# tdlf_03_05_2021_server.net
KiCad netlist of a schematic drawn in EAGLE
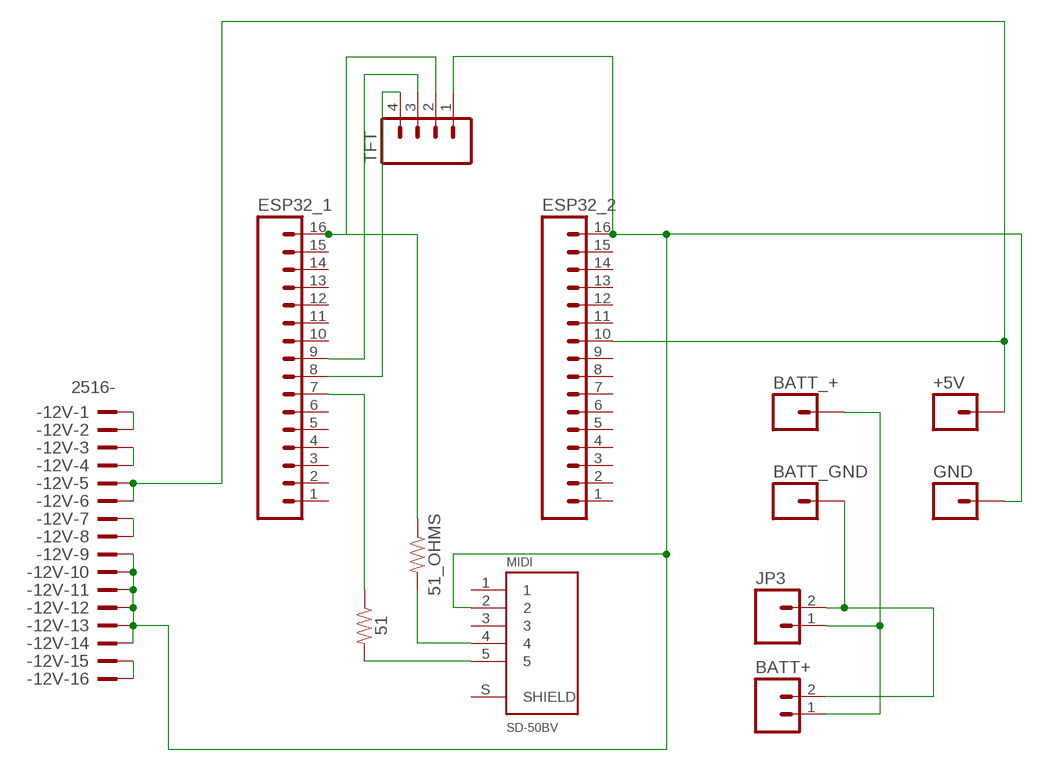
[diagram p0: schematic, sheet 1]

(export (version "E")
  (design (tool "Eeschema 10.0.6"))
  (components
    (comp (ref "+5V")
      (value "M01PTH")
      (footprint "eagle-import:1X01")
      (libsource (lib "eagle-import") (part "M01PTH"))
    )
    (comp (ref "-12V")
      (value "2516-")
      (footprint "eagle-import:PAK100_2500-16")
      (libsource (lib "eagle-import") (part "2516-"))
    )
    (comp (ref "51")
      (value "RESISTOR1206")
      (footprint "eagle-import:1206")
      (libsource (lib "eagle-import") (part "RESISTOR1206"))
    )
    (comp (ref "51_OHMS")
      (value "RESISTOR1206")
      (footprint "eagle-import:1206")
      (libsource (lib "eagle-import") (part "RESISTOR1206"))
    )
    (comp (ref "BATT+")
      (value "M02PTH")
      (footprint "eagle-import:1X02")
      (libsource (lib "eagle-import") (part "M02PTH"))
    )
    (comp (ref "BATT_+")
      (value "M01PTH")
      (footprint "eagle-import:1X01")
      (libsource (lib "eagle-import") (part "M01PTH"))
    )
    (comp (ref "BATT_GND")
      (value "M01PTH")
      (footprint "eagle-import:1X01")
      (libsource (lib "eagle-import") (part "M01PTH"))
    )
    (comp (ref "ESP32_1")
      (value "M16PTH")
      (footprint "eagle-import:1X16")
      (libsource (lib "eagle-import") (part "M16PTH"))
    )
    (comp (ref "ESP32_2")
      (value "M16PTH")
      (footprint "eagle-import:1X16")
      (libsource (lib "eagle-import") (part "M16PTH"))
    )
    (comp (ref "GND")
      (value "M01PTH")
      (footprint "eagle-import:1X01")
      (libsource (lib "eagle-import") (part "M01PTH"))
    )
    (comp (ref "JP3")
      (value "M02PTH")
      (footprint "eagle-import:1X02")
      (libsource (lib "eagle-import") (part "M02PTH"))
    )
    (comp (ref "MIDI")
      (value "SD-50BV")
      (footprint "eagle-import:CUI_SD-50BV")
      (fields (field (name "MF") "CUI Inc"))
      (libsource (lib "eagle-import") (part "SD-50BV"))
    )
    (comp (ref "TFT")
      (value "M04PTH")
      (footprint "eagle-import:1X04")
      (libsource (lib "eagle-import") (part "M04PTH"))
    )
  )
  (nets
    (net (code "1") (name "Net-(-12VA-KL)") (class "Default")
      (node (ref "-12V") (pin "1") (pinfunction "KL_1") (pintype "passive"))
      (node (ref "-12V") (pin "2") (pinfunction "KL_2") (pintype "passive"))
    )
    (net (code "2") (name "Net-(-12VB-KL)") (class "Default")
      (node (ref "-12V") (pin "10") (pinfunction "KL_10") (pintype "passive"))
      (node (ref "-12V") (pin "11") (pinfunction "KL_11") (pintype "passive"))
      (node (ref "-12V") (pin "12") (pinfunction "KL_12") (pintype "passive"))
      (node (ref "-12V") (pin "13") (pinfunction "KL_13") (pintype "passive"))
      (node (ref "-12V") (pin "14") (pinfunction "KL_14") (pintype "passive"))
      (node (ref "-12V") (pin "9") (pinfunction "KL_9") (pintype "passive"))
      (node (ref "ESP32_2") (pin "16") (pinfunction "16_16") (pintype "passive"))
      (node (ref "GND") (pin "1") (pinfunction "1_1") (pintype "passive"))
      (node (ref "MIDI") (pin "2") (pinfunction "2_2") (pintype "passive"))
      (node (ref "TFT") (pin "1") (pinfunction "1_1") (pintype "passive"))
    )
    (net (code "3") (name "Net-(-12VG-KL)") (class "Default")
      (node (ref "-12V") (pin "15") (pinfunction "KL_15") (pintype "passive"))
      (node (ref "-12V") (pin "16") (pinfunction "KL_16") (pintype "passive"))
    )
    (net (code "4") (name "Net-(-12VJ-KL)") (class "Default")
      (node (ref "-12V") (pin "3") (pinfunction "KL_3") (pintype "passive"))
      (node (ref "-12V") (pin "4") (pinfunction "KL_4") (pintype "passive"))
    )
    (net (code "5") (name "Net-(-12VL-KL)") (class "Default")
      (node (ref "+5V") (pin "1") (pinfunction "1_1") (pintype "passive"))
      (node (ref "-12V") (pin "5") (pinfunction "KL_5") (pintype "passive"))
      (node (ref "-12V") (pin "6") (pinfunction "KL_6") (pintype "passive"))
      (node (ref "ESP32_2") (pin "10") (pinfunction "10_10") (pintype "passive"))
    )
    (net (code "6") (name "Net-(-12VN-KL)") (class "Default")
      (node (ref "-12V") (pin "7") (pinfunction "KL_7") (pintype "passive"))
      (node (ref "-12V") (pin "8") (pinfunction "KL_8") (pintype "passive"))
    )
    (net (code "7") (name "Net-(51-Pad1)") (class "Default")
      (node (ref "51") (pin "1") (pinfunction "1_1") (pintype "passive"))
      (node (ref "ESP32_1") (pin "7") (pinfunction "7_7") (pintype "passive"))
    )
    (net (code "8") (name "Net-(51-Pad2)") (class "Default")
      (node (ref "51") (pin "2") (pinfunction "2_2") (pintype "passive"))
      (node (ref "MIDI") (pin "5") (pinfunction "5_5") (pintype "passive"))
    )
    (net (code "9") (name "Net-(51_OHMS-Pad1)") (class "Default")
      (node (ref "51_OHMS") (pin "1") (pinfunction "1_1") (pintype "passive"))
      (node (ref "ESP32_1") (pin "16") (pinfunction "16_16") (pintype "passive"))
      (node (ref "TFT") (pin "2") (pinfunction "2_2") (pintype "passive"))
    )
    (net (code "10") (name "Net-(51_OHMS-Pad2)") (class "Default")
      (node (ref "51_OHMS") (pin "2") (pinfunction "2_2") (pintype "passive"))
      (node (ref "MIDI") (pin "4") (pinfunction "4_4") (pintype "passive"))
    )
    (net (code "11") (name "Net-(BATT+-Pad1)") (class "Default")
      (node (ref "BATT+") (pin "1") (pinfunction "1_1") (pintype "passive"))
      (node (ref "BATT_+") (pin "1") (pinfunction "1_1") (pintype "passive"))
      (node (ref "JP3") (pin "1") (pinfunction "1_1") (pintype "passive"))
    )
    (net (code "12") (name "Net-(BATT+-Pad2)") (class "Default")
      (node (ref "BATT+") (pin "2") (pinfunction "2_2") (pintype "passive"))
      (node (ref "BATT_GND") (pin "1") (pinfunction "1_1") (pintype "passive"))
      (node (ref "JP3") (pin "2") (pinfunction "2_2") (pintype "passive"))
    )
    (net (code "13") (name "Net-(ESP32_1-Pad8)") (class "Default")
      (node (ref "ESP32_1") (pin "8") (pinfunction "8_8") (pintype "passive"))
      (node (ref "TFT") (pin "4") (pinfunction "4_4") (pintype "passive"))
    )
    (net (code "14") (name "Net-(ESP32_1-Pad9)") (class "Default")
      (node (ref "ESP32_1") (pin "9") (pinfunction "9_9") (pintype "passive"))
      (node (ref "TFT") (pin "3") (pinfunction "3_3") (pintype "passive"))
    )
    (net (code "15") (name "unconnected-(ESP32_1-Pad1)") (class "Default")
      (node (ref "ESP32_1") (pin "1") (pinfunction "1_1") (pintype "passive"))
    )
    (net (code "16") (name "unconnected-(ESP32_1-Pad2)") (class "Default")
      (node (ref "ESP32_1") (pin "2") (pinfunction "2_2") (pintype "passive"))
    )
    (net (code "17") (name "unconnected-(ESP32_1-Pad3)") (class "Default")
      (node (ref "ESP32_1") (pin "3") (pinfunction "3_3") (pintype "passive"))
    )
    (net (code "18") (name "unconnected-(ESP32_1-Pad4)") (class "Default")
      (node (ref "ESP32_1") (pin "4") (pinfunction "4_4") (pintype "passive"))
    )
    (net (code "19") (name "unconnected-(ESP32_1-Pad5)") (class "Default")
      (node (ref "ESP32_1") (pin "5") (pinfunction "5_5") (pintype "passive"))
    )
    (net (code "20") (name "unconnected-(ESP32_1-Pad6)") (class "Default")
      (node (ref "ESP32_1") (pin "6") (pinfunction "6_6") (pintype "passive"))
    )
    (net (code "21") (name "unconnected-(ESP32_1-Pad10)") (class "Default")
      (node (ref "ESP32_1") (pin "10") (pinfunction "10_10") (pintype "passive"))
    )
    (net (code "22") (name "unconnected-(ESP32_1-Pad11)") (class "Default")
      (node (ref "ESP32_1") (pin "11") (pinfunction "11_11") (pintype "passive"))
    )
    (net (code "23") (name "unconnected-(ESP32_1-Pad12)") (class "Default")
      (node (ref "ESP32_1") (pin "12") (pinfunction "12_12") (pintype "passive"))
    )
    (net (code "24") (name "unconnected-(ESP32_1-Pad13)") (class "Default")
      (node (ref "ESP32_1") (pin "13") (pinfunction "13_13") (pintype "passive"))
    )
    (net (code "25") (name "unconnected-(ESP32_1-Pad14)") (class "Default")
      (node (ref "ESP32_1") (pin "14") (pinfunction "14_14") (pintype "passive"))
    )
    (net (code "26") (name "unconnected-(ESP32_1-Pad15)") (class "Default")
      (node (ref "ESP32_1") (pin "15") (pinfunction "15_15") (pintype "passive"))
    )
    (net (code "27") (name "unconnected-(ESP32_2-Pad1)") (class "Default")
      (node (ref "ESP32_2") (pin "1") (pinfunction "1_1") (pintype "passive"))
    )
    (net (code "28") (name "unconnected-(ESP32_2-Pad2)") (class "Default")
      (node (ref "ESP32_2") (pin "2") (pinfunction "2_2") (pintype "passive"))
    )
    (net (code "29") (name "unconnected-(ESP32_2-Pad3)") (class "Default")
      (node (ref "ESP32_2") (pin "3") (pinfunction "3_3") (pintype "passive"))
    )
    (net (code "30") (name "unconnected-(ESP32_2-Pad4)") (class "Default")
      (node (ref "ESP32_2") (pin "4") (pinfunction "4_4") (pintype "passive"))
    )
    (net (code "31") (name "unconnected-(ESP32_2-Pad5)") (class "Default")
      (node (ref "ESP32_2") (pin "5") (pinfunction "5_5") (pintype "passive"))
    )
    (net (code "32") (name "unconnected-(ESP32_2-Pad6)") (class "Default")
      (node (ref "ESP32_2") (pin "6") (pinfunction "6_6") (pintype "passive"))
    )
    (net (code "33") (name "unconnected-(ESP32_2-Pad7)") (class "Default")
      (node (ref "ESP32_2") (pin "7") (pinfunction "7_7") (pintype "passive"))
    )
    (net (code "34") (name "unconnected-(ESP32_2-Pad8)") (class "Default")
      (node (ref "ESP32_2") (pin "8") (pinfunction "8_8") (pintype "passive"))
    )
    (net (code "35") (name "unconnected-(ESP32_2-Pad9)") (class "Default")
      (node (ref "ESP32_2") (pin "9") (pinfunction "9_9") (pintype "passive"))
    )
    (net (code "36") (name "unconnected-(ESP32_2-Pad11)") (class "Default")
      (node (ref "ESP32_2") (pin "11") (pinfunction "11_11") (pintype "passive"))
    )
    (net (code "37") (name "unconnected-(ESP32_2-Pad12)") (class "Default")
      (node (ref "ESP32_2") (pin "12") (pinfunction "12_12") (pintype "passive"))
    )
    (net (code "38") (name "unconnected-(ESP32_2-Pad13)") (class "Default")
      (node (ref "ESP32_2") (pin "13") (pinfunction "13_13") (pintype "passive"))
    )
    (net (code "39") (name "unconnected-(ESP32_2-Pad14)") (class "Default")
      (node (ref "ESP32_2") (pin "14") (pinfunction "14_14") (pintype "passive"))
    )
    (net (code "40") (name "unconnected-(ESP32_2-Pad15)") (class "Default")
      (node (ref "ESP32_2") (pin "15") (pinfunction "15_15") (pintype "passive"))
    )
    (net (code "41") (name "unconnected-(MIDI-Pad1)") (class "Default")
      (node (ref "MIDI") (pin "1") (pinfunction "1_1") (pintype "passive"))
    )
    (net (code "42") (name "unconnected-(MIDI-Pad3)") (class "Default")
      (node (ref "MIDI") (pin "3") (pinfunction "3_3") (pintype "passive"))
    )
    (net (code "43") (name "unconnected-(MIDI-SHIELD-PadS)") (class "Default")
      (node (ref "MIDI") (pin "S") (pinfunction "SHIELD_S") (pintype "passive"))
    )
  )
)
